# DAC.net
KiCad netlist of a schematic drawn in Altium Designer
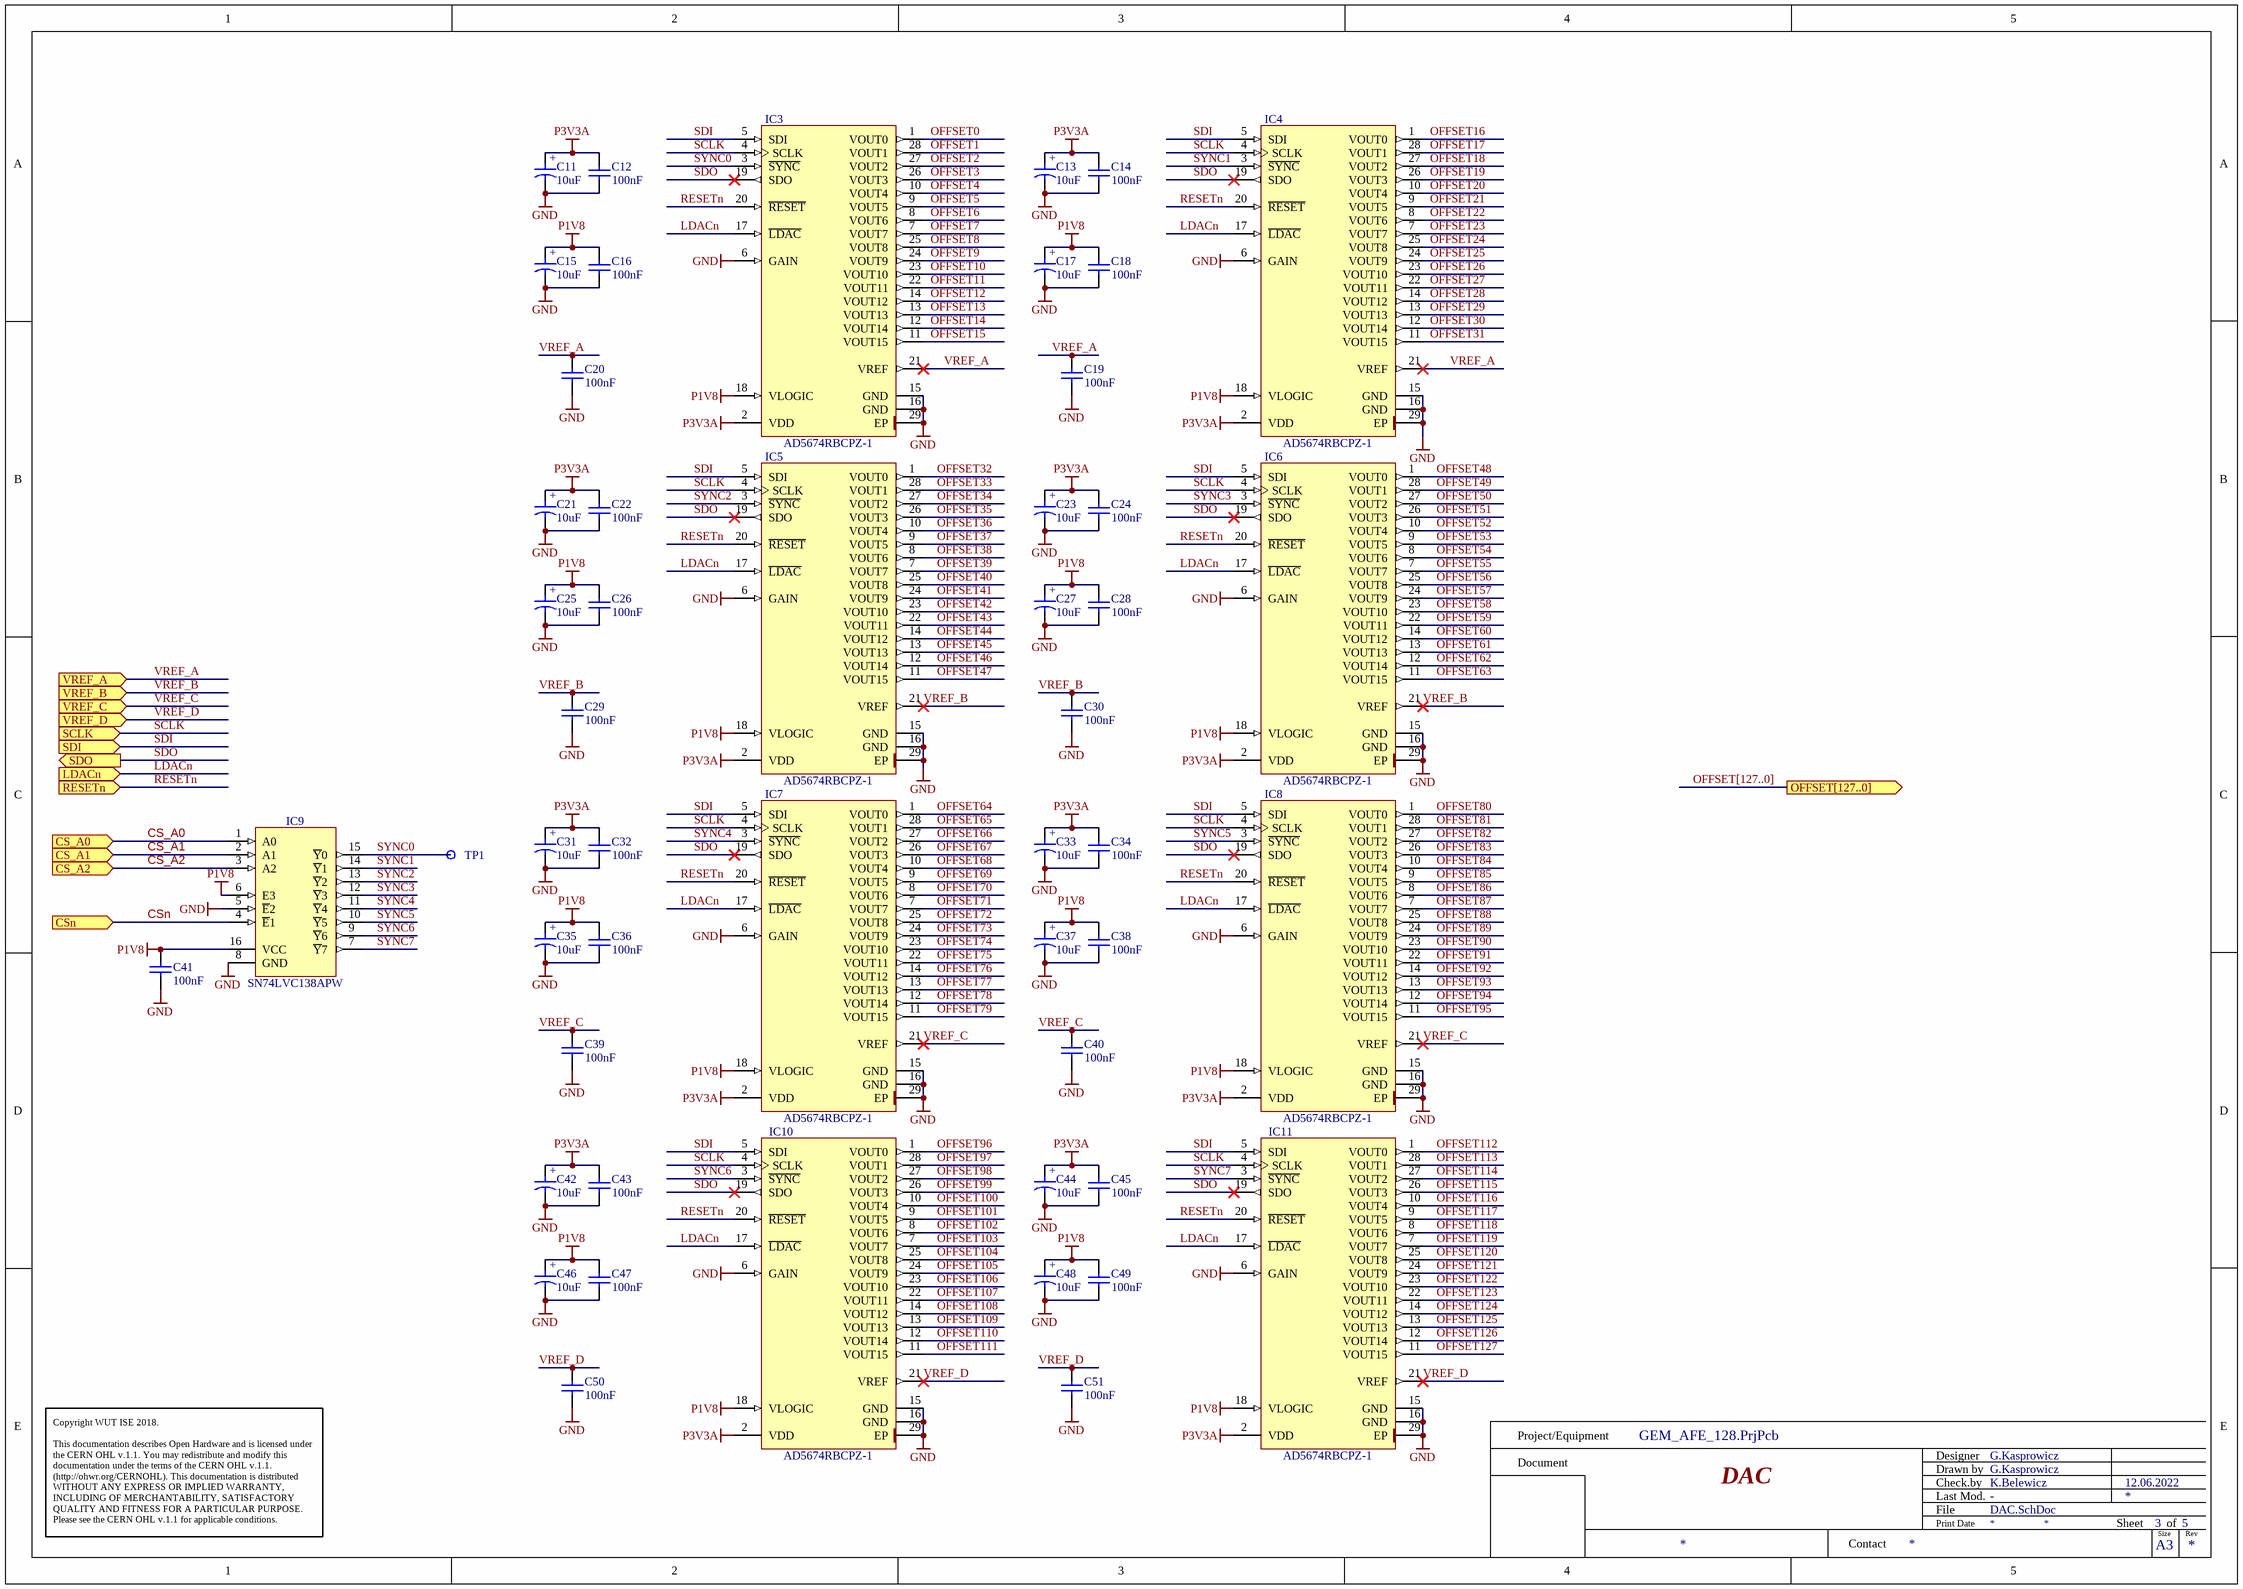
[diagram p0: DAC.SchDoc]

(export (version "E")
  (design (tool "Eeschema 10.0.6"))
  (components
    (comp (ref "C11")
      (value "10uF")
      (footprint "CAPMP3216X180N")
      (description "Polarised capacitor")
      (fields
        (field (name "PART NUMBER") "CTE3216-18_10UF_16V_20%_AVX_TCJ")
        (field (name "VOLTAGE") "16V")
        (field (name "AUTHOR") "CERN DEM JLC")
      )
      (libsource (lib "Capacitors") (part "Capacitor - polarized"))
    )
    (comp (ref "C12")
      (value "100nF")
      (footprint "CAPC1005X55N")
      (description "Non-polarised capacitor")
      (fields
        (field (name "PART NUMBER") "CC0402_100NF_6.3V_10%_X7R")
        (field (name "VOLTAGE") "6.3V")
        (field (name "AUTHOR") "CERN DEM BC")
      )
      (libsource (lib "Capacitors") (part "Capacitor - non polarized"))
    )
    (comp (ref "C13")
      (value "10uF")
      (footprint "CAPMP3216X180N")
      (description "Polarised capacitor")
      (fields
        (field (name "PART NUMBER") "CTE3216-18_10UF_16V_20%_AVX_TCJ")
        (field (name "VOLTAGE") "16V")
        (field (name "AUTHOR") "CERN DEM JLC")
      )
      (libsource (lib "Capacitors") (part "Capacitor - polarized"))
    )
    (comp (ref "C14")
      (value "100nF")
      (footprint "CAPC1005X55N")
      (description "Non-polarised capacitor")
      (fields
        (field (name "PART NUMBER") "CC0402_100NF_6.3V_10%_X7R")
        (field (name "VOLTAGE") "6.3V")
        (field (name "AUTHOR") "CERN DEM BC")
      )
      (libsource (lib "Capacitors") (part "Capacitor - non polarized"))
    )
    (comp (ref "C15")
      (value "10uF")
      (footprint "CAPMP3216X180N")
      (description "Polarised capacitor")
      (fields
        (field (name "PART NUMBER") "CTE3216-18_10UF_16V_20%_AVX_TCJ")
        (field (name "VOLTAGE") "16V")
        (field (name "AUTHOR") "CERN DEM JLC")
      )
      (libsource (lib "Capacitors") (part "Capacitor - polarized"))
    )
    (comp (ref "C16")
      (value "100nF")
      (footprint "CAPC1005X55N")
      (description "Non-polarised capacitor")
      (fields
        (field (name "PART NUMBER") "CC0402_100NF_6.3V_10%_X7R")
        (field (name "VOLTAGE") "6.3V")
        (field (name "AUTHOR") "CERN DEM BC")
      )
      (libsource (lib "Capacitors") (part "Capacitor - non polarized"))
    )
    (comp (ref "C17")
      (value "10uF")
      (footprint "CAPMP3216X180N")
      (description "Polarised capacitor")
      (fields
        (field (name "PART NUMBER") "CTE3216-18_10UF_16V_20%_AVX_TCJ")
        (field (name "VOLTAGE") "16V")
        (field (name "AUTHOR") "CERN DEM JLC")
      )
      (libsource (lib "Capacitors") (part "Capacitor - polarized"))
    )
    (comp (ref "C18")
      (value "100nF")
      (footprint "CAPC1005X55N")
      (description "Non-polarised capacitor")
      (fields
        (field (name "PART NUMBER") "CC0402_100NF_6.3V_10%_X7R")
        (field (name "VOLTAGE") "6.3V")
        (field (name "AUTHOR") "CERN DEM BC")
      )
      (libsource (lib "Capacitors") (part "Capacitor - non polarized"))
    )
    (comp (ref "C19")
      (value "100nF")
      (footprint "CAPC1005X55N")
      (description "Non-polarised capacitor")
      (fields
        (field (name "PART NUMBER") "CC0402_100NF_6.3V_10%_X7R")
        (field (name "VOLTAGE") "6.3V")
        (field (name "AUTHOR") "CERN DEM BC")
      )
      (libsource (lib "Capacitors") (part "Capacitor - non polarized"))
    )
    (comp (ref "C20")
      (value "100nF")
      (footprint "CAPC1005X55N")
      (description "Non-polarised capacitor")
      (fields
        (field (name "PART NUMBER") "CC0402_100NF_6.3V_10%_X7R")
        (field (name "VOLTAGE") "6.3V")
        (field (name "AUTHOR") "CERN DEM BC")
      )
      (libsource (lib "Capacitors") (part "Capacitor - non polarized"))
    )
    (comp (ref "C21")
      (value "10uF")
      (footprint "CAPMP3216X180N")
      (description "Polarised capacitor")
      (fields
        (field (name "PART NUMBER") "CTE3216-18_10UF_16V_20%_AVX_TCJ")
        (field (name "VOLTAGE") "16V")
        (field (name "AUTHOR") "CERN DEM JLC")
      )
      (libsource (lib "Capacitors") (part "Capacitor - polarized"))
    )
    (comp (ref "C22")
      (value "100nF")
      (footprint "CAPC1005X55N")
      (description "Non-polarised capacitor")
      (fields
        (field (name "PART NUMBER") "CC0402_100NF_6.3V_10%_X7R")
        (field (name "VOLTAGE") "6.3V")
        (field (name "AUTHOR") "CERN DEM BC")
      )
      (libsource (lib "Capacitors") (part "Capacitor - non polarized"))
    )
    (comp (ref "C23")
      (value "10uF")
      (footprint "CAPMP3216X180N")
      (description "Polarised capacitor")
      (fields
        (field (name "PART NUMBER") "CTE3216-18_10UF_16V_20%_AVX_TCJ")
        (field (name "VOLTAGE") "16V")
        (field (name "AUTHOR") "CERN DEM JLC")
      )
      (libsource (lib "Capacitors") (part "Capacitor - polarized"))
    )
    (comp (ref "C24")
      (value "100nF")
      (footprint "CAPC1005X55N")
      (description "Non-polarised capacitor")
      (fields
        (field (name "PART NUMBER") "CC0402_100NF_6.3V_10%_X7R")
        (field (name "VOLTAGE") "6.3V")
        (field (name "AUTHOR") "CERN DEM BC")
      )
      (libsource (lib "Capacitors") (part "Capacitor - non polarized"))
    )
    (comp (ref "C25")
      (value "10uF")
      (footprint "CAPMP3216X180N")
      (description "Polarised capacitor")
      (fields
        (field (name "PART NUMBER") "CTE3216-18_10UF_16V_20%_AVX_TCJ")
        (field (name "VOLTAGE") "16V")
        (field (name "AUTHOR") "CERN DEM JLC")
      )
      (libsource (lib "Capacitors") (part "Capacitor - polarized"))
    )
    (comp (ref "C26")
      (value "100nF")
      (footprint "CAPC1005X55N")
      (description "Non-polarised capacitor")
      (fields
        (field (name "PART NUMBER") "CC0402_100NF_6.3V_10%_X7R")
        (field (name "VOLTAGE") "6.3V")
        (field (name "AUTHOR") "CERN DEM BC")
      )
      (libsource (lib "Capacitors") (part "Capacitor - non polarized"))
    )
    (comp (ref "C27")
      (value "10uF")
      (footprint "CAPMP3216X180N")
      (description "Polarised capacitor")
      (fields
        (field (name "PART NUMBER") "CTE3216-18_10UF_16V_20%_AVX_TCJ")
        (field (name "VOLTAGE") "16V")
        (field (name "AUTHOR") "CERN DEM JLC")
      )
      (libsource (lib "Capacitors") (part "Capacitor - polarized"))
    )
    (comp (ref "C28")
      (value "100nF")
      (footprint "CAPC1005X55N")
      (description "Non-polarised capacitor")
      (fields
        (field (name "PART NUMBER") "CC0402_100NF_6.3V_10%_X7R")
        (field (name "VOLTAGE") "6.3V")
        (field (name "AUTHOR") "CERN DEM BC")
      )
      (libsource (lib "Capacitors") (part "Capacitor - non polarized"))
    )
    (comp (ref "C29")
      (value "100nF")
      (footprint "CAPC1005X55N")
      (description "Non-polarised capacitor")
      (fields
        (field (name "PART NUMBER") "CC0402_100NF_6.3V_10%_X7R")
        (field (name "VOLTAGE") "6.3V")
        (field (name "AUTHOR") "CERN DEM BC")
      )
      (libsource (lib "Capacitors") (part "Capacitor - non polarized"))
    )
    (comp (ref "C30")
      (value "100nF")
      (footprint "CAPC1005X55N")
      (description "Non-polarised capacitor")
      (fields
        (field (name "PART NUMBER") "CC0402_100NF_6.3V_10%_X7R")
        (field (name "VOLTAGE") "6.3V")
        (field (name "AUTHOR") "CERN DEM BC")
      )
      (libsource (lib "Capacitors") (part "Capacitor - non polarized"))
    )
    (comp (ref "C31")
      (value "10uF")
      (footprint "CAPMP3216X180N")
      (description "Polarised capacitor")
      (fields
        (field (name "PART NUMBER") "CTE3216-18_10UF_16V_20%_AVX_TCJ")
        (field (name "VOLTAGE") "16V")
        (field (name "AUTHOR") "CERN DEM JLC")
      )
      (libsource (lib "Capacitors") (part "Capacitor - polarized"))
    )
    (comp (ref "C32")
      (value "100nF")
      (footprint "CAPC1005X55N")
      (description "Non-polarised capacitor")
      (fields
        (field (name "PART NUMBER") "CC0402_100NF_6.3V_10%_X7R")
        (field (name "VOLTAGE") "6.3V")
        (field (name "AUTHOR") "CERN DEM BC")
      )
      (libsource (lib "Capacitors") (part "Capacitor - non polarized"))
    )
    (comp (ref "C33")
      (value "10uF")
      (footprint "CAPMP3216X180N")
      (description "Polarised capacitor")
      (fields
        (field (name "PART NUMBER") "CTE3216-18_10UF_16V_20%_AVX_TCJ")
        (field (name "VOLTAGE") "16V")
        (field (name "AUTHOR") "CERN DEM JLC")
      )
      (libsource (lib "Capacitors") (part "Capacitor - polarized"))
    )
    (comp (ref "C34")
      (value "100nF")
      (footprint "CAPC1005X55N")
      (description "Non-polarised capacitor")
      (fields
        (field (name "PART NUMBER") "CC0402_100NF_6.3V_10%_X7R")
        (field (name "VOLTAGE") "6.3V")
        (field (name "AUTHOR") "CERN DEM BC")
      )
      (libsource (lib "Capacitors") (part "Capacitor - non polarized"))
    )
    (comp (ref "C35")
      (value "10uF")
      (footprint "CAPMP3216X180N")
      (description "Polarised capacitor")
      (fields
        (field (name "PART NUMBER") "CTE3216-18_10UF_16V_20%_AVX_TCJ")
        (field (name "VOLTAGE") "16V")
        (field (name "AUTHOR") "CERN DEM JLC")
      )
      (libsource (lib "Capacitors") (part "Capacitor - polarized"))
    )
    (comp (ref "C36")
      (value "100nF")
      (footprint "CAPC1005X55N")
      (description "Non-polarised capacitor")
      (fields
        (field (name "PART NUMBER") "CC0402_100NF_6.3V_10%_X7R")
        (field (name "VOLTAGE") "6.3V")
        (field (name "AUTHOR") "CERN DEM BC")
      )
      (libsource (lib "Capacitors") (part "Capacitor - non polarized"))
    )
    (comp (ref "C37")
      (value "10uF")
      (footprint "CAPMP3216X180N")
      (description "Polarised capacitor")
      (fields
        (field (name "PART NUMBER") "CTE3216-18_10UF_16V_20%_AVX_TCJ")
        (field (name "VOLTAGE") "16V")
        (field (name "AUTHOR") "CERN DEM JLC")
      )
      (libsource (lib "Capacitors") (part "Capacitor - polarized"))
    )
    (comp (ref "C38")
      (value "100nF")
      (footprint "CAPC1005X55N")
      (description "Non-polarised capacitor")
      (fields
        (field (name "PART NUMBER") "CC0402_100NF_6.3V_10%_X7R")
        (field (name "VOLTAGE") "6.3V")
        (field (name "AUTHOR") "CERN DEM BC")
      )
      (libsource (lib "Capacitors") (part "Capacitor - non polarized"))
    )
    (comp (ref "C39")
      (value "100nF")
      (footprint "CAPC1005X55N")
      (description "Non-polarised capacitor")
      (fields
        (field (name "PART NUMBER") "CC0402_100NF_6.3V_10%_X7R")
        (field (name "VOLTAGE") "6.3V")
        (field (name "AUTHOR") "CERN DEM BC")
      )
      (libsource (lib "Capacitors") (part "Capacitor - non polarized"))
    )
    (comp (ref "C40")
      (value "100nF")
      (footprint "CAPC1005X55N")
      (description "Non-polarised capacitor")
      (fields
        (field (name "PART NUMBER") "CC0402_100NF_6.3V_10%_X7R")
        (field (name "VOLTAGE") "6.3V")
        (field (name "AUTHOR") "CERN DEM BC")
      )
      (libsource (lib "Capacitors") (part "Capacitor - non polarized"))
    )
    (comp (ref "C41")
      (value "100nF")
      (footprint "CAPC1005X55N")
      (description "Non-polarised capacitor")
      (fields
        (field (name "PART NUMBER") "CC0402_100NF_16V_10%_X5R")
        (field (name "VOLTAGE") "16V")
        (field (name "AUTHOR") "CERN DEM JLC")
      )
      (libsource (lib "Capacitors") (part "Capacitor - non polarized"))
    )
    (comp (ref "C42")
      (value "10uF")
      (footprint "CAPMP3216X180N")
      (description "Polarised capacitor")
      (fields
        (field (name "PART NUMBER") "CTE3216-18_10UF_16V_20%_AVX_TCJ")
        (field (name "VOLTAGE") "16V")
        (field (name "AUTHOR") "CERN DEM JLC")
      )
      (libsource (lib "Capacitors") (part "Capacitor - polarized"))
    )
    (comp (ref "C43")
      (value "100nF")
      (footprint "CAPC1005X55N")
      (description "Non-polarised capacitor")
      (fields
        (field (name "PART NUMBER") "CC0402_100NF_6.3V_10%_X7R")
        (field (name "VOLTAGE") "6.3V")
        (field (name "AUTHOR") "CERN DEM BC")
      )
      (libsource (lib "Capacitors") (part "Capacitor - non polarized"))
    )
    (comp (ref "C44")
      (value "10uF")
      (footprint "CAPMP3216X180N")
      (description "Polarised capacitor")
      (fields
        (field (name "PART NUMBER") "CTE3216-18_10UF_16V_20%_AVX_TCJ")
        (field (name "VOLTAGE") "16V")
        (field (name "AUTHOR") "CERN DEM JLC")
      )
      (libsource (lib "Capacitors") (part "Capacitor - polarized"))
    )
    (comp (ref "C45")
      (value "100nF")
      (footprint "CAPC1005X55N")
      (description "Non-polarised capacitor")
      (fields
        (field (name "PART NUMBER") "CC0402_100NF_6.3V_10%_X7R")
        (field (name "VOLTAGE") "6.3V")
        (field (name "AUTHOR") "CERN DEM BC")
      )
      (libsource (lib "Capacitors") (part "Capacitor - non polarized"))
    )
    (comp (ref "C46")
      (value "10uF")
      (footprint "CAPMP3216X180N")
      (description "Polarised capacitor")
      (fields
        (field (name "PART NUMBER") "CTE3216-18_10UF_16V_20%_AVX_TCJ")
        (field (name "VOLTAGE") "16V")
        (field (name "AUTHOR") "CERN DEM JLC")
      )
      (libsource (lib "Capacitors") (part "Capacitor - polarized"))
    )
    (comp (ref "C47")
      (value "100nF")
      (footprint "CAPC1005X55N")
      (description "Non-polarised capacitor")
      (fields
        (field (name "PART NUMBER") "CC0402_100NF_6.3V_10%_X7R")
        (field (name "VOLTAGE") "6.3V")
        (field (name "AUTHOR") "CERN DEM BC")
      )
      (libsource (lib "Capacitors") (part "Capacitor - non polarized"))
    )
    (comp (ref "C48")
      (value "10uF")
      (footprint "CAPMP3216X180N")
      (description "Polarised capacitor")
      (fields
        (field (name "PART NUMBER") "CTE3216-18_10UF_16V_20%_AVX_TCJ")
        (field (name "VOLTAGE") "16V")
        (field (name "AUTHOR") "CERN DEM JLC")
      )
      (libsource (lib "Capacitors") (part "Capacitor - polarized"))
    )
    (comp (ref "C49")
      (value "100nF")
      (footprint "CAPC1005X55N")
      (description "Non-polarised capacitor")
      (fields
        (field (name "PART NUMBER") "CC0402_100NF_6.3V_10%_X7R")
        (field (name "VOLTAGE") "6.3V")
        (field (name "AUTHOR") "CERN DEM BC")
      )
      (libsource (lib "Capacitors") (part "Capacitor - non polarized"))
    )
    (comp (ref "C50")
      (value "100nF")
      (footprint "CAPC1005X55N")
      (description "Non-polarised capacitor")
      (fields
        (field (name "PART NUMBER") "CC0402_100NF_6.3V_10%_X7R")
        (field (name "VOLTAGE") "6.3V")
        (field (name "AUTHOR") "CERN DEM BC")
      )
      (libsource (lib "Capacitors") (part "Capacitor - non polarized"))
    )
    (comp (ref "C51")
      (value "100nF")
      (footprint "CAPC1005X55N")
      (description "Non-polarised capacitor")
      (fields
        (field (name "PART NUMBER") "CC0402_100NF_6.3V_10%_X7R")
        (field (name "VOLTAGE") "6.3V")
        (field (name "AUTHOR") "CERN DEM BC")
      )
      (libsource (lib "Capacitors") (part "Capacitor - non polarized"))
    )
    (comp (ref "IC3")
      (value "AD5674RBCPZ-1")
      (footprint "QFN40P400X400X100-29N-S270")
      (description "12-Bit nanoDAC+ with 2 ppm/°C Voltage Reference Temperature Coefficient, SPI Interface")
      (fields (field (name "MANUFACTURER") "ANALOG DEVICES") (field (name "AUTHOR") "CERN DEM HF"))
      (libsource (lib "ICs And Semiconductors") (part "AD5674RBCPZ-1"))
    )
    (comp (ref "IC4")
      (value "AD5674RBCPZ-1")
      (footprint "QFN40P400X400X100-29N-S270")
      (description "12-Bit nanoDAC+ with 2 ppm/°C Voltage Reference Temperature Coefficient, SPI Interface")
      (fields (field (name "MANUFACTURER") "ANALOG DEVICES") (field (name "AUTHOR") "CERN DEM HF"))
      (libsource (lib "ICs And Semiconductors") (part "AD5674RBCPZ-1"))
    )
    (comp (ref "IC5")
      (value "AD5674RBCPZ-1")
      (footprint "QFN40P400X400X100-29N-S270")
      (description "12-Bit nanoDAC+ with 2 ppm/°C Voltage Reference Temperature Coefficient, SPI Interface")
      (fields (field (name "MANUFACTURER") "ANALOG DEVICES") (field (name "AUTHOR") "CERN DEM HF"))
      (libsource (lib "ICs And Semiconductors") (part "AD5674RBCPZ-1"))
    )
    (comp (ref "IC6")
      (value "AD5674RBCPZ-1")
      (footprint "QFN40P400X400X100-29N-S270")
      (description "12-Bit nanoDAC+ with 2 ppm/°C Voltage Reference Temperature Coefficient, SPI Interface")
      (fields (field (name "MANUFACTURER") "ANALOG DEVICES") (field (name "AUTHOR") "CERN DEM HF"))
      (libsource (lib "ICs And Semiconductors") (part "AD5674RBCPZ-1"))
    )
    (comp (ref "IC7")
      (value "AD5674RBCPZ-1")
      (footprint "QFN40P400X400X100-29N-S270")
      (description "12-Bit nanoDAC+ with 2 ppm/°C Voltage Reference Temperature Coefficient, SPI Interface")
      (fields (field (name "MANUFACTURER") "ANALOG DEVICES") (field (name "AUTHOR") "CERN DEM HF"))
      (libsource (lib "ICs And Semiconductors") (part "AD5674RBCPZ-1"))
    )
    (comp (ref "IC8")
      (value "AD5674RBCPZ-1")
      (footprint "QFN40P400X400X100-29N-S270")
      (description "12-Bit nanoDAC+ with 2 ppm/°C Voltage Reference Temperature Coefficient, SPI Interface")
      (fields (field (name "MANUFACTURER") "ANALOG DEVICES") (field (name "AUTHOR") "CERN DEM HF"))
      (libsource (lib "ICs And Semiconductors") (part "AD5674RBCPZ-1"))
    )
    (comp (ref "IC9")
      (value "SN74LVC138APW")
      (footprint "SOP65P640X110-16N")
      (description "3-Line to 8-Line Decoder/Demultiplexer")
      (fields (field (name "MANUFACTURER") "Texas Instruments") (field (name "AUTHOR") "GK"))
      (libsource (lib "ICS-logic") (part "SN74LVC138APW"))
    )
    (comp (ref "IC10")
      (value "AD5674RBCPZ-1")
      (footprint "QFN40P400X400X100-29N-S270")
      (description "12-Bit nanoDAC+ with 2 ppm/°C Voltage Reference Temperature Coefficient, SPI Interface")
      (fields (field (name "MANUFACTURER") "ANALOG DEVICES") (field (name "AUTHOR") "CERN DEM HF"))
      (libsource (lib "ICs And Semiconductors") (part "AD5674RBCPZ-1"))
    )
    (comp (ref "IC11")
      (value "AD5674RBCPZ-1")
      (footprint "QFN40P400X400X100-29N-S270")
      (description "12-Bit nanoDAC+ with 2 ppm/°C Voltage Reference Temperature Coefficient, SPI Interface")
      (fields (field (name "MANUFACTURER") "ANALOG DEVICES") (field (name "AUTHOR") "CERN DEM HF"))
      (libsource (lib "ICs And Semiconductors") (part "AD5674RBCPZ-1"))
    )
    (comp (ref "TP1")
      (value "Test Point")
      (footprint "TPS127")
      (fields (field (name "PART NUMBER") "SMD_PAD_1.27X1.27MM") (field (name "AUTHOR") "CERN DEM JLC"))
      (libsource (lib "Eletro-mechanical") (part "Test Point"))
    )
  )
  (nets
    (net (code "1") (name "/CS_A0") (class "Default")
      (node (ref "IC9") (pin "1") (pinfunction "A0_1") (pintype "input"))
    )
    (net (code "2") (name "/CS_A1") (class "Default")
      (node (ref "IC9") (pin "2") (pinfunction "A1_2") (pintype "input"))
    )
    (net (code "3") (name "/CS_A2") (class "Default")
      (node (ref "IC9") (pin "3") (pinfunction "A2_3") (pintype "input"))
    )
    (net (code "4") (name "/CSn") (class "Default")
      (node (ref "IC9") (pin "4") (pinfunction "~{E}1_4") (pintype "input"))
    )
    (net (code "5") (name "/LDACn") (class "Default")
      (node (ref "IC10") (pin "17") (pinfunction "~{LDAC}_17") (pintype "input"))
      (node (ref "IC11") (pin "17") (pinfunction "~{LDAC}_17") (pintype "input"))
      (node (ref "IC3") (pin "17") (pinfunction "~{LDAC}_17") (pintype "input"))
      (node (ref "IC4") (pin "17") (pinfunction "~{LDAC}_17") (pintype "input"))
      (node (ref "IC5") (pin "17") (pinfunction "~{LDAC}_17") (pintype "input"))
      (node (ref "IC6") (pin "17") (pinfunction "~{LDAC}_17") (pintype "input"))
      (node (ref "IC7") (pin "17") (pinfunction "~{LDAC}_17") (pintype "input"))
      (node (ref "IC8") (pin "17") (pinfunction "~{LDAC}_17") (pintype "input"))
    )
    (net (code "6") (name "/OFFSET0") (class "Default")
      (node (ref "IC3") (pin "1") (pinfunction "VOUT0_1") (pintype "output"))
    )
    (net (code "7") (name "/OFFSET1") (class "Default")
      (node (ref "IC3") (pin "28") (pinfunction "VOUT1_28") (pintype "output"))
    )
    (net (code "8") (name "/OFFSET2") (class "Default")
      (node (ref "IC3") (pin "27") (pinfunction "VOUT2_27") (pintype "output"))
    )
    (net (code "9") (name "/OFFSET3") (class "Default")
      (node (ref "IC3") (pin "26") (pinfunction "VOUT3_26") (pintype "output"))
    )
    (net (code "10") (name "/OFFSET4") (class "Default")
      (node (ref "IC3") (pin "10") (pinfunction "VOUT4_10") (pintype "output"))
    )
    (net (code "11") (name "/OFFSET5") (class "Default")
      (node (ref "IC3") (pin "9") (pinfunction "VOUT5_9") (pintype "output"))
    )
    (net (code "12") (name "/OFFSET6") (class "Default")
      (node (ref "IC3") (pin "8") (pinfunction "VOUT6_8") (pintype "output"))
    )
    (net (code "13") (name "/OFFSET7") (class "Default")
      (node (ref "IC3") (pin "7") (pinfunction "VOUT7_7") (pintype "output"))
    )
    (net (code "14") (name "/OFFSET8") (class "Default")
      (node (ref "IC3") (pin "25") (pinfunction "VOUT8_25") (pintype "output"))
    )
    (net (code "15") (name "/OFFSET9") (class "Default")
      (node (ref "IC3") (pin "24") (pinfunction "VOUT9_24") (pintype "output"))
    )
    (net (code "16") (name "/OFFSET10") (class "Default")
      (node (ref "IC3") (pin "23") (pinfunction "VOUT10_23") (pintype "output"))
    )
    (net (code "17") (name "/OFFSET11") (class "Default")
      (node (ref "IC3") (pin "22") (pinfunction "VOUT11_22") (pintype "output"))
    )
    (net (code "18") (name "/OFFSET12") (class "Default")
      (node (ref "IC3") (pin "14") (pinfunction "VOUT12_14") (pintype "output"))
    )
    (net (code "19") (name "/OFFSET13") (class "Default")
      (node (ref "IC3") (pin "13") (pinfunction "VOUT13_13") (pintype "output"))
    )
    (net (code "20") (name "/OFFSET14") (class "Default")
      (node (ref "IC3") (pin "12") (pinfunction "VOUT14_12") (pintype "output"))
    )
    (net (code "21") (name "/OFFSET15") (class "Default")
      (node (ref "IC3") (pin "11") (pinfunction "VOUT15_11") (pintype "output"))
    )
    (net (code "22") (name "/OFFSET16") (class "Default")
      (node (ref "IC4") (pin "1") (pinfunction "VOUT0_1") (pintype "output"))
    )
    (net (code "23") (name "/OFFSET17") (class "Default")
      (node (ref "IC4") (pin "28") (pinfunction "VOUT1_28") (pintype "output"))
    )
    (net (code "24") (name "/OFFSET18") (class "Default")
      (node (ref "IC4") (pin "27") (pinfunction "VOUT2_27") (pintype "output"))
    )
    (net (code "25") (name "/OFFSET19") (class "Default")
      (node (ref "IC4") (pin "26") (pinfunction "VOUT3_26") (pintype "output"))
    )
    (net (code "26") (name "/OFFSET20") (class "Default")
      (node (ref "IC4") (pin "10") (pinfunction "VOUT4_10") (pintype "output"))
    )
    (net (code "27") (name "/OFFSET21") (class "Default")
      (node (ref "IC4") (pin "9") (pinfunction "VOUT5_9") (pintype "output"))
    )
    (net (code "28") (name "/OFFSET22") (class "Default")
      (node (ref "IC4") (pin "8") (pinfunction "VOUT6_8") (pintype "output"))
    )
    (net (code "29") (name "/OFFSET23") (class "Default")
      (node (ref "IC4") (pin "7") (pinfunction "VOUT7_7") (pintype "output"))
    )
    (net (code "30") (name "/OFFSET24") (class "Default")
      (node (ref "IC4") (pin "25") (pinfunction "VOUT8_25") (pintype "output"))
    )
    (net (code "31") (name "/OFFSET25") (class "Default")
      (node (ref "IC4") (pin "24") (pinfunction "VOUT9_24") (pintype "output"))
    )
    (net (code "32") (name "/OFFSET26") (class "Default")
      (node (ref "IC4") (pin "23") (pinfunction "VOUT10_23") (pintype "output"))
    )
    (net (code "33") (name "/OFFSET27") (class "Default")
      (node (ref "IC4") (pin "22") (pinfunction "VOUT11_22") (pintype "output"))
    )
    (net (code "34") (name "/OFFSET28") (class "Default")
      (node (ref "IC4") (pin "14") (pinfunction "VOUT12_14") (pintype "output"))
    )
    (net (code "35") (name "/OFFSET29") (class "Default")
      (node (ref "IC4") (pin "13") (pinfunction "VOUT13_13") (pintype "output"))
    )
    (net (code "36") (name "/OFFSET30") (class "Default")
      (node (ref "IC4") (pin "12") (pinfunction "VOUT14_12") (pintype "output"))
    )
    (net (code "37") (name "/OFFSET31") (class "Default")
      (node (ref "IC4") (pin "11") (pinfunction "VOUT15_11") (pintype "output"))
    )
    (net (code "38") (name "/OFFSET32") (class "Default")
      (node (ref "IC5") (pin "1") (pinfunction "VOUT0_1") (pintype "output"))
    )
    (net (code "39") (name "/OFFSET33") (class "Default")
      (node (ref "IC5") (pin "28") (pinfunction "VOUT1_28") (pintype "output"))
    )
    (net (code "40") (name "/OFFSET34") (class "Default")
      (node (ref "IC5") (pin "27") (pinfunction "VOUT2_27") (pintype "output"))
    )
    (net (code "41") (name "/OFFSET35") (class "Default")
      (node (ref "IC5") (pin "26") (pinfunction "VOUT3_26") (pintype "output"))
    )
    (net (code "42") (name "/OFFSET36") (class "Default")
      (node (ref "IC5") (pin "10") (pinfunction "VOUT4_10") (pintype "output"))
    )
    (net (code "43") (name "/OFFSET37") (class "Default")
      (node (ref "IC5") (pin "9") (pinfunction "VOUT5_9") (pintype "output"))
    )
    (net (code "44") (name "/OFFSET38") (class "Default")
      (node (ref "IC5") (pin "8") (pinfunction "VOUT6_8") (pintype "output"))
    )
    (net (code "45") (name "/OFFSET39") (class "Default")
      (node (ref "IC5") (pin "7") (pinfunction "VOUT7_7") (pintype "output"))
    )
    (net (code "46") (name "/OFFSET40") (class "Default")
      (node (ref "IC5") (pin "25") (pinfunction "VOUT8_25") (pintype "output"))
    )
    (net (code "47") (name "/OFFSET41") (class "Default")
      (node (ref "IC5") (pin "24") (pinfunction "VOUT9_24") (pintype "output"))
    )
    (net (code "48") (name "/OFFSET42") (class "Default")
      (node (ref "IC5") (pin "23") (pinfunction "VOUT10_23") (pintype "output"))
    )
    (net (code "49") (name "/OFFSET43") (class "Default")
      (node (ref "IC5") (pin "22") (pinfunction "VOUT11_22") (pintype "output"))
    )
    (net (code "50") (name "/OFFSET44") (class "Default")
      (node (ref "IC5") (pin "14") (pinfunction "VOUT12_14") (pintype "output"))
    )
    (net (code "51") (name "/OFFSET45") (class "Default")
      (node (ref "IC5") (pin "13") (pinfunction "VOUT13_13") (pintype "output"))
    )
    (net (code "52") (name "/OFFSET46") (class "Default")
      (node (ref "IC5") (pin "12") (pinfunction "VOUT14_12") (pintype "output"))
    )
    (net (code "53") (name "/OFFSET47") (class "Default")
      (node (ref "IC5") (pin "11") (pinfunction "VOUT15_11") (pintype "output"))
    )
    (net (code "54") (name "/OFFSET48") (class "Default")
      (node (ref "IC6") (pin "1") (pinfunction "VOUT0_1") (pintype "output"))
    )
    (net (code "55") (name "/OFFSET49") (class "Default")
      (node (ref "IC6") (pin "28") (pinfunction "VOUT1_28") (pintype "output"))
    )
    (net (code "56") (name "/OFFSET50") (class "Default")
      (node (ref "IC6") (pin "27") (pinfunction "VOUT2_27") (pintype "output"))
    )
    (net (code "57") (name "/OFFSET51") (class "Default")
      (node (ref "IC6") (pin "26") (pinfunction "VOUT3_26") (pintype "output"))
    )
    (net (code "58") (name "/OFFSET52") (class "Default")
      (node (ref "IC6") (pin "10") (pinfunction "VOUT4_10") (pintype "output"))
    )
    (net (code "59") (name "/OFFSET53") (class "Default")
      (node (ref "IC6") (pin "9") (pinfunction "VOUT5_9") (pintype "output"))
    )
    (net (code "60") (name "/OFFSET54") (class "Default")
      (node (ref "IC6") (pin "8") (pinfunction "VOUT6_8") (pintype "output"))
    )
    (net (code "61") (name "/OFFSET55") (class "Default")
      (node (ref "IC6") (pin "7") (pinfunction "VOUT7_7") (pintype "output"))
    )
    (net (code "62") (name "/OFFSET56") (class "Default")
      (node (ref "IC6") (pin "25") (pinfunction "VOUT8_25") (pintype "output"))
    )
    (net (code "63") (name "/OFFSET57") (class "Default")
      (node (ref "IC6") (pin "24") (pinfunction "VOUT9_24") (pintype "output"))
    )
    (net (code "64") (name "/OFFSET58") (class "Default")
      (node (ref "IC6") (pin "23") (pinfunction "VOUT10_23") (pintype "output"))
    )
    (net (code "65") (name "/OFFSET59") (class "Default")
      (node (ref "IC6") (pin "22") (pinfunction "VOUT11_22") (pintype "output"))
    )
    (net (code "66") (name "/OFFSET60") (class "Default")
      (node (ref "IC6") (pin "14") (pinfunction "VOUT12_14") (pintype "output"))
    )
    (net (code "67") (name "/OFFSET61") (class "Default")
      (node (ref "IC6") (pin "13") (pinfunction "VOUT13_13") (pintype "output"))
    )
    (net (code "68") (name "/OFFSET62") (class "Default")
      (node (ref "IC6") (pin "12") (pinfunction "VOUT14_12") (pintype "output"))
    )
    (net (code "69") (name "/OFFSET63") (class "Default")
      (node (ref "IC6") (pin "11") (pinfunction "VOUT15_11") (pintype "output"))
    )
    (net (code "70") (name "/OFFSET64") (class "Default")
      (node (ref "IC7") (pin "1") (pinfunction "VOUT0_1") (pintype "output"))
    )
    (net (code "71") (name "/OFFSET65") (class "Default")
      (node (ref "IC7") (pin "28") (pinfunction "VOUT1_28") (pintype "output"))
    )
    (net (code "72") (name "/OFFSET66") (class "Default")
      (node (ref "IC7") (pin "27") (pinfunction "VOUT2_27") (pintype "output"))
    )
    (net (code "73") (name "/OFFSET67") (class "Default")
      (node (ref "IC7") (pin "26") (pinfunction "VOUT3_26") (pintype "output"))
    )
    (net (code "74") (name "/OFFSET68") (class "Default")
      (node (ref "IC7") (pin "10") (pinfunction "VOUT4_10") (pintype "output"))
    )
    (net (code "75") (name "/OFFSET69") (class "Default")
      (node (ref "IC7") (pin "9") (pinfunction "VOUT5_9") (pintype "output"))
    )
    (net (code "76") (name "/OFFSET70") (class "Default")
      (node (ref "IC7") (pin "8") (pinfunction "VOUT6_8") (pintype "output"))
    )
    (net (code "77") (name "/OFFSET71") (class "Default")
      (node (ref "IC7") (pin "7") (pinfunction "VOUT7_7") (pintype "output"))
    )
    (net (code "78") (name "/OFFSET72") (class "Default")
      (node (ref "IC7") (pin "25") (pinfunction "VOUT8_25") (pintype "output"))
    )
    (net (code "79") (name "/OFFSET73") (class "Default")
      (node (ref "IC7") (pin "24") (pinfunction "VOUT9_24") (pintype "output"))
    )
    (net (code "80") (name "/OFFSET74") (class "Default")
      (node (ref "IC7") (pin "23") (pinfunction "VOUT10_23") (pintype "output"))
    )
    (net (code "81") (name "/OFFSET75") (class "Default")
      (node (ref "IC7") (pin "22") (pinfunction "VOUT11_22") (pintype "output"))
    )
    (net (code "82") (name "/OFFSET76") (class "Default")
      (node (ref "IC7") (pin "14") (pinfunction "VOUT12_14") (pintype "output"))
    )
    (net (code "83") (name "/OFFSET77") (class "Default")
      (node (ref "IC7") (pin "13") (pinfunction "VOUT13_13") (pintype "output"))
    )
    (net (code "84") (name "/OFFSET78") (class "Default")
      (node (ref "IC7") (pin "12") (pinfunction "VOUT14_12") (pintype "output"))
    )
    (net (code "85") (name "/OFFSET79") (class "Default")
      (node (ref "IC7") (pin "11") (pinfunction "VOUT15_11") (pintype "output"))
    )
    (net (code "86") (name "/OFFSET80") (class "Default")
      (node (ref "IC8") (pin "1") (pinfunction "VOUT0_1") (pintype "output"))
    )
    (net (code "87") (name "/OFFSET81") (class "Default")
      (node (ref "IC8") (pin "28") (pinfunction "VOUT1_28") (pintype "output"))
    )
    (net (code "88") (name "/OFFSET82") (class "Default")
      (node (ref "IC8") (pin "27") (pinfunction "VOUT2_27") (pintype "output"))
    )
    (net (code "89") (name "/OFFSET83") (class "Default")
      (node (ref "IC8") (pin "26") (pinfunction "VOUT3_26") (pintype "output"))
    )
    (net (code "90") (name "/OFFSET84") (class "Default")
      (node (ref "IC8") (pin "10") (pinfunction "VOUT4_10") (pintype "output"))
    )
    (net (code "91") (name "/OFFSET85") (class "Default")
      (node (ref "IC8") (pin "9") (pinfunction "VOUT5_9") (pintype "output"))
    )
    (net (code "92") (name "/OFFSET86") (class "Default")
      (node (ref "IC8") (pin "8") (pinfunction "VOUT6_8") (pintype "output"))
    )
    (net (code "93") (name "/OFFSET87") (class "Default")
      (node (ref "IC8") (pin "7") (pinfunction "VOUT7_7") (pintype "output"))
    )
    (net (code "94") (name "/OFFSET88") (class "Default")
      (node (ref "IC8") (pin "25") (pinfunction "VOUT8_25") (pintype "output"))
    )
    (net (code "95") (name "/OFFSET89") (class "Default")
      (node (ref "IC8") (pin "24") (pinfunction "VOUT9_24") (pintype "output"))
    )
    (net (code "96") (name "/OFFSET90") (class "Default")
      (node (ref "IC8") (pin "23") (pinfunction "VOUT10_23") (pintype "output"))
    )
    (net (code "97") (name "/OFFSET91") (class "Default")
      (node (ref "IC8") (pin "22") (pinfunction "VOUT11_22") (pintype "output"))
    )
    (net (code "98") (name "/OFFSET92") (class "Default")
      (node (ref "IC8") (pin "14") (pinfunction "VOUT12_14") (pintype "output"))
    )
    (net (code "99") (name "/OFFSET93") (class "Default")
      (node (ref "IC8") (pin "13") (pinfunction "VOUT13_13") (pintype "output"))
    )
    (net (code "100") (name "/OFFSET94") (class "Default")
      (node (ref "IC8") (pin "12") (pinfunction "VOUT14_12") (pintype "output"))
    )
    (net (code "101") (name "/OFFSET95") (class "Default")
      (node (ref "IC8") (pin "11") (pinfunction "VOUT15_11") (pintype "output"))
    )
    (net (code "102") (name "/OFFSET96") (class "Default")
      (node (ref "IC10") (pin "1") (pinfunction "VOUT0_1") (pintype "output"))
    )
    (net (code "103") (name "/OFFSET97") (class "Default")
      (node (ref "IC10") (pin "28") (pinfunction "VOUT1_28") (pintype "output"))
    )
    (net (code "104") (name "/OFFSET98") (class "Default")
      (node (ref "IC10") (pin "27") (pinfunction "VOUT2_27") (pintype "output"))
    )
    (net (code "105") (name "/OFFSET99") (class "Default")
      (node (ref "IC10") (pin "26") (pinfunction "VOUT3_26") (pintype "output"))
    )
    (net (code "106") (name "/OFFSET100") (class "Default")
      (node (ref "IC10") (pin "10") (pinfunction "VOUT4_10") (pintype "output"))
    )
    (net (code "107") (name "/OFFSET101") (class "Default")
      (node (ref "IC10") (pin "9") (pinfunction "VOUT5_9") (pintype "output"))
    )
    (net (code "108") (name "/OFFSET102") (class "Default")
      (node (ref "IC10") (pin "8") (pinfunction "VOUT6_8") (pintype "output"))
    )
    (net (code "109") (name "/OFFSET103") (class "Default")
      (node (ref "IC10") (pin "7") (pinfunction "VOUT7_7") (pintype "output"))
    )
    (net (code "110") (name "/OFFSET104") (class "Default")
      (node (ref "IC10") (pin "25") (pinfunction "VOUT8_25") (pintype "output"))
    )
    (net (code "111") (name "/OFFSET105") (class "Default")
      (node (ref "IC10") (pin "24") (pinfunction "VOUT9_24") (pintype "output"))
    )
    (net (code "112") (name "/OFFSET106") (class "Default")
      (node (ref "IC10") (pin "23") (pinfunction "VOUT10_23") (pintype "output"))
    )
    (net (code "113") (name "/OFFSET107") (class "Default")
      (node (ref "IC10") (pin "22") (pinfunction "VOUT11_22") (pintype "output"))
    )
    (net (code "114") (name "/OFFSET108") (class "Default")
      (node (ref "IC10") (pin "14") (pinfunction "VOUT12_14") (pintype "output"))
    )
    (net (code "115") (name "/OFFSET109") (class "Default")
      (node (ref "IC10") (pin "13") (pinfunction "VOUT13_13") (pintype "output"))
    )
    (net (code "116") (name "/OFFSET110") (class "Default")
      (node (ref "IC10") (pin "12") (pinfunction "VOUT14_12") (pintype "output"))
    )
    (net (code "117") (name "/OFFSET111") (class "Default")
      (node (ref "IC10") (pin "11") (pinfunction "VOUT15_11") (pintype "output"))
    )
    (net (code "118") (name "/OFFSET112") (class "Default")
      (node (ref "IC11") (pin "1") (pinfunction "VOUT0_1") (pintype "output"))
    )
    (net (code "119") (name "/OFFSET113") (class "Default")
      (node (ref "IC11") (pin "28") (pinfunction "VOUT1_28") (pintype "output"))
    )
    (net (code "120") (name "/OFFSET114") (class "Default")
      (node (ref "IC11") (pin "27") (pinfunction "VOUT2_27") (pintype "output"))
    )
    (net (code "121") (name "/OFFSET115") (class "Default")
      (node (ref "IC11") (pin "26") (pinfunction "VOUT3_26") (pintype "output"))
    )
    (net (code "122") (name "/OFFSET116") (class "Default")
      (node (ref "IC11") (pin "10") (pinfunction "VOUT4_10") (pintype "output"))
    )
    (net (code "123") (name "/OFFSET117") (class "Default")
      (node (ref "IC11") (pin "9") (pinfunction "VOUT5_9") (pintype "output"))
    )
    (net (code "124") (name "/OFFSET118") (class "Default")
      (node (ref "IC11") (pin "8") (pinfunction "VOUT6_8") (pintype "output"))
    )
    (net (code "125") (name "/OFFSET119") (class "Default")
      (node (ref "IC11") (pin "7") (pinfunction "VOUT7_7") (pintype "output"))
    )
    (net (code "126") (name "/OFFSET120") (class "Default")
      (node (ref "IC11") (pin "25") (pinfunction "VOUT8_25") (pintype "output"))
    )
    (net (code "127") (name "/OFFSET121") (class "Default")
      (node (ref "IC11") (pin "24") (pinfunction "VOUT9_24") (pintype "output"))
    )
    (net (code "128") (name "/OFFSET122") (class "Default")
      (node (ref "IC11") (pin "23") (pinfunction "VOUT10_23") (pintype "output"))
    )
    (net (code "129") (name "/OFFSET123") (class "Default")
      (node (ref "IC11") (pin "22") (pinfunction "VOUT11_22") (pintype "output"))
    )
    (net (code "130") (name "/OFFSET124") (class "Default")
      (node (ref "IC11") (pin "14") (pinfunction "VOUT12_14") (pintype "output"))
    )
    (net (code "131") (name "/OFFSET125") (class "Default")
      (node (ref "IC11") (pin "13") (pinfunction "VOUT13_13") (pintype "output"))
    )
    (net (code "132") (name "/OFFSET126") (class "Default")
      (node (ref "IC11") (pin "12") (pinfunction "VOUT14_12") (pintype "output"))
    )
    (net (code "133") (name "/OFFSET127") (class "Default")
      (node (ref "IC11") (pin "11") (pinfunction "VOUT15_11") (pintype "output"))
    )
    (net (code "135") (name "/RESETn") (class "Default")
      (node (ref "IC10") (pin "20") (pinfunction "~{RESET}_20") (pintype "input"))
      (node (ref "IC11") (pin "20") (pinfunction "~{RESET}_20") (pintype "input"))
      (node (ref "IC3") (pin "20") (pinfunction "~{RESET}_20") (pintype "input"))
      (node (ref "IC4") (pin "20") (pinfunction "~{RESET}_20") (pintype "input"))
      (node (ref "IC5") (pin "20") (pinfunction "~{RESET}_20") (pintype "input"))
      (node (ref "IC6") (pin "20") (pinfunction "~{RESET}_20") (pintype "input"))
      (node (ref "IC7") (pin "20") (pinfunction "~{RESET}_20") (pintype "input"))
      (node (ref "IC8") (pin "20") (pinfunction "~{RESET}_20") (pintype "input"))
    )
    (net (code "136") (name "/SCLK") (class "Default")
      (node (ref "IC10") (pin "4") (pinfunction "SCLK_4") (pintype "input"))
      (node (ref "IC11") (pin "4") (pinfunction "SCLK_4") (pintype "input"))
      (node (ref "IC3") (pin "4") (pinfunction "SCLK_4") (pintype "input"))
      (node (ref "IC4") (pin "4") (pinfunction "SCLK_4") (pintype "input"))
      (node (ref "IC5") (pin "4") (pinfunction "SCLK_4") (pintype "input"))
      (node (ref "IC6") (pin "4") (pinfunction "SCLK_4") (pintype "input"))
      (node (ref "IC7") (pin "4") (pinfunction "SCLK_4") (pintype "input"))
      (node (ref "IC8") (pin "4") (pinfunction "SCLK_4") (pintype "input"))
    )
    (net (code "137") (name "/SDI") (class "Default")
      (node (ref "IC10") (pin "5") (pinfunction "SDI_5") (pintype "input"))
      (node (ref "IC11") (pin "5") (pinfunction "SDI_5") (pintype "input"))
      (node (ref "IC3") (pin "5") (pinfunction "SDI_5") (pintype "input"))
      (node (ref "IC4") (pin "5") (pinfunction "SDI_5") (pintype "input"))
      (node (ref "IC5") (pin "5") (pinfunction "SDI_5") (pintype "input"))
      (node (ref "IC6") (pin "5") (pinfunction "SDI_5") (pintype "input"))
      (node (ref "IC7") (pin "5") (pinfunction "SDI_5") (pintype "input"))
      (node (ref "IC8") (pin "5") (pinfunction "SDI_5") (pintype "input"))
    )
    (net (code "138") (name "/SDO") (class "Default")
      (node (ref "IC10") (pin "19") (pinfunction "SDO_19") (pintype "output"))
      (node (ref "IC11") (pin "19") (pinfunction "SDO_19") (pintype "output"))
      (node (ref "IC3") (pin "19") (pinfunction "SDO_19") (pintype "output"))
      (node (ref "IC4") (pin "19") (pinfunction "SDO_19") (pintype "output"))
      (node (ref "IC5") (pin "19") (pinfunction "SDO_19") (pintype "output"))
      (node (ref "IC6") (pin "19") (pinfunction "SDO_19") (pintype "output"))
      (node (ref "IC7") (pin "19") (pinfunction "SDO_19") (pintype "output"))
      (node (ref "IC8") (pin "19") (pinfunction "SDO_19") (pintype "output"))
    )
    (net (code "139") (name "/SYNC0") (class "Default")
      (node (ref "IC3") (pin "3") (pinfunction "~{SYNC}_3") (pintype "input"))
      (node (ref "IC9") (pin "15") (pinfunction "~{Y}0_15") (pintype "output"))
      (node (ref "TP1") (pin "1") (pinfunction "1_1") (pintype "bidirectional"))
    )
    (net (code "140") (name "/SYNC1") (class "Default")
      (node (ref "IC4") (pin "3") (pinfunction "~{SYNC}_3") (pintype "input"))
      (node (ref "IC9") (pin "14") (pinfunction "~{Y}1_14") (pintype "output"))
    )
    (net (code "141") (name "/SYNC2") (class "Default")
      (node (ref "IC5") (pin "3") (pinfunction "~{SYNC}_3") (pintype "input"))
      (node (ref "IC9") (pin "13") (pinfunction "~{Y}2_13") (pintype "output"))
    )
    (net (code "142") (name "/SYNC3") (class "Default")
      (node (ref "IC6") (pin "3") (pinfunction "~{SYNC}_3") (pintype "input"))
      (node (ref "IC9") (pin "12") (pinfunction "~{Y}3_12") (pintype "output"))
    )
    (net (code "143") (name "/SYNC4") (class "Default")
      (node (ref "IC7") (pin "3") (pinfunction "~{SYNC}_3") (pintype "input"))
      (node (ref "IC9") (pin "11") (pinfunction "~{Y}4_11") (pintype "output"))
    )
    (net (code "144") (name "/SYNC5") (class "Default")
      (node (ref "IC8") (pin "3") (pinfunction "~{SYNC}_3") (pintype "input"))
      (node (ref "IC9") (pin "10") (pinfunction "~{Y}5_10") (pintype "output"))
    )
    (net (code "145") (name "/SYNC6") (class "Default")
      (node (ref "IC10") (pin "3") (pinfunction "~{SYNC}_3") (pintype "input"))
      (node (ref "IC9") (pin "9") (pinfunction "~{Y}6_9") (pintype "output"))
    )
    (net (code "146") (name "/SYNC7") (class "Default")
      (node (ref "IC11") (pin "3") (pinfunction "~{SYNC}_3") (pintype "input"))
      (node (ref "IC9") (pin "7") (pinfunction "~{Y}7_7") (pintype "output"))
    )
    (net (code "147") (name "/VREF_A") (class "Default")
      (node (ref "C19") (pin "2") (pinfunction "2_2") (pintype "passive"))
      (node (ref "C20") (pin "2") (pinfunction "2_2") (pintype "passive"))
      (node (ref "IC3") (pin "21") (pinfunction "VREF_21") (pintype "output"))
      (node (ref "IC4") (pin "21") (pinfunction "VREF_21") (pintype "output"))
    )
    (net (code "148") (name "/VREF_B") (class "Default")
      (node (ref "C29") (pin "2") (pinfunction "2_2") (pintype "passive"))
      (node (ref "C30") (pin "2") (pinfunction "2_2") (pintype "passive"))
      (node (ref "IC5") (pin "21") (pinfunction "VREF_21") (pintype "output"))
      (node (ref "IC6") (pin "21") (pinfunction "VREF_21") (pintype "output"))
    )
    (net (code "149") (name "/VREF_C") (class "Default")
      (node (ref "C39") (pin "2") (pinfunction "2_2") (pintype "passive"))
      (node (ref "C40") (pin "2") (pinfunction "2_2") (pintype "passive"))
      (node (ref "IC7") (pin "21") (pinfunction "VREF_21") (pintype "output"))
      (node (ref "IC8") (pin "21") (pinfunction "VREF_21") (pintype "output"))
    )
    (net (code "150") (name "/VREF_D") (class "Default")
      (node (ref "C50") (pin "2") (pinfunction "2_2") (pintype "passive"))
      (node (ref "C51") (pin "2") (pinfunction "2_2") (pintype "passive"))
      (node (ref "IC10") (pin "21") (pinfunction "VREF_21") (pintype "output"))
      (node (ref "IC11") (pin "21") (pinfunction "VREF_21") (pintype "output"))
    )
    (net (code "151") (name "GND") (class "Default")
      (node (ref "C11") (pin "2") (pinfunction "2_2") (pintype "passive"))
      (node (ref "C12") (pin "1") (pinfunction "1_1") (pintype "passive"))
      (node (ref "C13") (pin "2") (pinfunction "2_2") (pintype "passive"))
      (node (ref "C14") (pin "1") (pinfunction "1_1") (pintype "passive"))
      (node (ref "C15") (pin "2") (pinfunction "2_2") (pintype "passive"))
      (node (ref "C16") (pin "1") (pinfunction "1_1") (pintype "passive"))
      (node (ref "C17") (pin "2") (pinfunction "2_2") (pintype "passive"))
      (node (ref "C18") (pin "1") (pinfunction "1_1") (pintype "passive"))
      (node (ref "C19") (pin "1") (pinfunction "1_1") (pintype "passive"))
      (node (ref "C20") (pin "1") (pinfunction "1_1") (pintype "passive"))
      (node (ref "C21") (pin "2") (pinfunction "2_2") (pintype "passive"))
      (node (ref "C22") (pin "1") (pinfunction "1_1") (pintype "passive"))
      (node (ref "C23") (pin "2") (pinfunction "2_2") (pintype "passive"))
      (node (ref "C24") (pin "1") (pinfunction "1_1") (pintype "passive"))
      (node (ref "C25") (pin "2") (pinfunction "2_2") (pintype "passive"))
      (node (ref "C26") (pin "1") (pinfunction "1_1") (pintype "passive"))
      (node (ref "C27") (pin "2") (pinfunction "2_2") (pintype "passive"))
      (node (ref "C28") (pin "1") (pinfunction "1_1") (pintype "passive"))
      (node (ref "C29") (pin "1") (pinfunction "1_1") (pintype "passive"))
      (node (ref "C30") (pin "1") (pinfunction "1_1") (pintype "passive"))
      (node (ref "C31") (pin "2") (pinfunction "2_2") (pintype "passive"))
      (node (ref "C32") (pin "1") (pinfunction "1_1") (pintype "passive"))
      (node (ref "C33") (pin "2") (pinfunction "2_2") (pintype "passive"))
      (node (ref "C34") (pin "1") (pinfunction "1_1") (pintype "passive"))
      (node (ref "C35") (pin "2") (pinfunction "2_2") (pintype "passive"))
      (node (ref "C36") (pin "1") (pinfunction "1_1") (pintype "passive"))
      (node (ref "C37") (pin "2") (pinfunction "2_2") (pintype "passive"))
      (node (ref "C38") (pin "1") (pinfunction "1_1") (pintype "passive"))
      (node (ref "C39") (pin "1") (pinfunction "1_1") (pintype "passive"))
      (node (ref "C40") (pin "1") (pinfunction "1_1") (pintype "passive"))
      (node (ref "C41") (pin "1") (pinfunction "1_1") (pintype "passive"))
      (node (ref "C42") (pin "2") (pinfunction "2_2") (pintype "passive"))
      (node (ref "C43") (pin "1") (pinfunction "1_1") (pintype "passive"))
      (node (ref "C44") (pin "2") (pinfunction "2_2") (pintype "passive"))
      (node (ref "C45") (pin "1") (pinfunction "1_1") (pintype "passive"))
      (node (ref "C46") (pin "2") (pinfunction "2_2") (pintype "passive"))
      (node (ref "C47") (pin "1") (pinfunction "1_1") (pintype "passive"))
      (node (ref "C48") (pin "2") (pinfunction "2_2") (pintype "passive"))
      (node (ref "C49") (pin "1") (pinfunction "1_1") (pintype "passive"))
      (node (ref "C50") (pin "1") (pinfunction "1_1") (pintype "passive"))
      (node (ref "C51") (pin "1") (pinfunction "1_1") (pintype "passive"))
      (node (ref "IC10") (pin "15") (pinfunction "GND_15") (pintype "power_in"))
      (node (ref "IC10") (pin "16") (pinfunction "GND_16") (pintype "power_in"))
      (node (ref "IC10") (pin "29") (pinfunction "EP_29") (pintype "power_in"))
      (node (ref "IC10") (pin "6") (pinfunction "GAIN_6") (pintype "input"))
      (node (ref "IC11") (pin "15") (pinfunction "GND_15") (pintype "power_in"))
      (node (ref "IC11") (pin "16") (pinfunction "GND_16") (pintype "power_in"))
      (node (ref "IC11") (pin "29") (pinfunction "EP_29") (pintype "power_in"))
      (node (ref "IC11") (pin "6") (pinfunction "GAIN_6") (pintype "input"))
      (node (ref "IC3") (pin "15") (pinfunction "GND_15") (pintype "power_in"))
      (node (ref "IC3") (pin "16") (pinfunction "GND_16") (pintype "power_in"))
      (node (ref "IC3") (pin "29") (pinfunction "EP_29") (pintype "power_in"))
      (node (ref "IC3") (pin "6") (pinfunction "GAIN_6") (pintype "input"))
      (node (ref "IC4") (pin "15") (pinfunction "GND_15") (pintype "power_in"))
      (node (ref "IC4") (pin "16") (pinfunction "GND_16") (pintype "power_in"))
      (node (ref "IC4") (pin "29") (pinfunction "EP_29") (pintype "power_in"))
      (node (ref "IC4") (pin "6") (pinfunction "GAIN_6") (pintype "input"))
      (node (ref "IC5") (pin "15") (pinfunction "GND_15") (pintype "power_in"))
      (node (ref "IC5") (pin "16") (pinfunction "GND_16") (pintype "power_in"))
      (node (ref "IC5") (pin "29") (pinfunction "EP_29") (pintype "power_in"))
      (node (ref "IC5") (pin "6") (pinfunction "GAIN_6") (pintype "input"))
      (node (ref "IC6") (pin "15") (pinfunction "GND_15") (pintype "power_in"))
      (node (ref "IC6") (pin "16") (pinfunction "GND_16") (pintype "power_in"))
      (node (ref "IC6") (pin "29") (pinfunction "EP_29") (pintype "power_in"))
      (node (ref "IC6") (pin "6") (pinfunction "GAIN_6") (pintype "input"))
      (node (ref "IC7") (pin "15") (pinfunction "GND_15") (pintype "power_in"))
      (node (ref "IC7") (pin "16") (pinfunction "GND_16") (pintype "power_in"))
      (node (ref "IC7") (pin "29") (pinfunction "EP_29") (pintype "power_in"))
      (node (ref "IC7") (pin "6") (pinfunction "GAIN_6") (pintype "input"))
      (node (ref "IC8") (pin "15") (pinfunction "GND_15") (pintype "power_in"))
      (node (ref "IC8") (pin "16") (pinfunction "GND_16") (pintype "power_in"))
      (node (ref "IC8") (pin "29") (pinfunction "EP_29") (pintype "power_in"))
      (node (ref "IC8") (pin "6") (pinfunction "GAIN_6") (pintype "input"))
      (node (ref "IC9") (pin "5") (pinfunction "~{E}2_5") (pintype "input"))
      (node (ref "IC9") (pin "8") (pinfunction "GND_8") (pintype "power_in"))
    )
    (net (code "152") (name "P1V8") (class "Default")
      (node (ref "C15") (pin "1") (pinfunction "1_1") (pintype "passive"))
      (node (ref "C16") (pin "2") (pinfunction "2_2") (pintype "passive"))
      (node (ref "C17") (pin "1") (pinfunction "1_1") (pintype "passive"))
      (node (ref "C18") (pin "2") (pinfunction "2_2") (pintype "passive"))
      (node (ref "C25") (pin "1") (pinfunction "1_1") (pintype "passive"))
      (node (ref "C26") (pin "2") (pinfunction "2_2") (pintype "passive"))
      (node (ref "C27") (pin "1") (pinfunction "1_1") (pintype "passive"))
      (node (ref "C28") (pin "2") (pinfunction "2_2") (pintype "passive"))
      (node (ref "C35") (pin "1") (pinfunction "1_1") (pintype "passive"))
      (node (ref "C36") (pin "2") (pinfunction "2_2") (pintype "passive"))
      (node (ref "C37") (pin "1") (pinfunction "1_1") (pintype "passive"))
      (node (ref "C38") (pin "2") (pinfunction "2_2") (pintype "passive"))
      (node (ref "C41") (pin "2") (pinfunction "2_2") (pintype "passive"))
      (node (ref "C46") (pin "1") (pinfunction "1_1") (pintype "passive"))
      (node (ref "C47") (pin "2") (pinfunction "2_2") (pintype "passive"))
      (node (ref "C48") (pin "1") (pinfunction "1_1") (pintype "passive"))
      (node (ref "C49") (pin "2") (pinfunction "2_2") (pintype "passive"))
      (node (ref "IC10") (pin "18") (pinfunction "VLOGIC_18") (pintype "input"))
      (node (ref "IC11") (pin "18") (pinfunction "VLOGIC_18") (pintype "input"))
      (node (ref "IC3") (pin "18") (pinfunction "VLOGIC_18") (pintype "input"))
      (node (ref "IC4") (pin "18") (pinfunction "VLOGIC_18") (pintype "input"))
      (node (ref "IC5") (pin "18") (pinfunction "VLOGIC_18") (pintype "input"))
      (node (ref "IC6") (pin "18") (pinfunction "VLOGIC_18") (pintype "input"))
      (node (ref "IC7") (pin "18") (pinfunction "VLOGIC_18") (pintype "input"))
      (node (ref "IC8") (pin "18") (pinfunction "VLOGIC_18") (pintype "input"))
      (node (ref "IC9") (pin "16") (pinfunction "VCC_16") (pintype "power_in"))
      (node (ref "IC9") (pin "6") (pinfunction "E3_6") (pintype "input"))
    )
    (net (code "153") (name "P3V3A") (class "Default")
      (node (ref "C11") (pin "1") (pinfunction "1_1") (pintype "passive"))
      (node (ref "C12") (pin "2") (pinfunction "2_2") (pintype "passive"))
      (node (ref "C13") (pin "1") (pinfunction "1_1") (pintype "passive"))
      (node (ref "C14") (pin "2") (pinfunction "2_2") (pintype "passive"))
      (node (ref "C21") (pin "1") (pinfunction "1_1") (pintype "passive"))
      (node (ref "C22") (pin "2") (pinfunction "2_2") (pintype "passive"))
      (node (ref "C23") (pin "1") (pinfunction "1_1") (pintype "passive"))
      (node (ref "C24") (pin "2") (pinfunction "2_2") (pintype "passive"))
      (node (ref "C31") (pin "1") (pinfunction "1_1") (pintype "passive"))
      (node (ref "C32") (pin "2") (pinfunction "2_2") (pintype "passive"))
      (node (ref "C33") (pin "1") (pinfunction "1_1") (pintype "passive"))
      (node (ref "C34") (pin "2") (pinfunction "2_2") (pintype "passive"))
      (node (ref "C42") (pin "1") (pinfunction "1_1") (pintype "passive"))
      (node (ref "C43") (pin "2") (pinfunction "2_2") (pintype "passive"))
      (node (ref "C44") (pin "1") (pinfunction "1_1") (pintype "passive"))
      (node (ref "C45") (pin "2") (pinfunction "2_2") (pintype "passive"))
      (node (ref "IC10") (pin "2") (pinfunction "VDD_2") (pintype "power_in"))
      (node (ref "IC11") (pin "2") (pinfunction "VDD_2") (pintype "power_in"))
      (node (ref "IC3") (pin "2") (pinfunction "VDD_2") (pintype "power_in"))
      (node (ref "IC4") (pin "2") (pinfunction "VDD_2") (pintype "power_in"))
      (node (ref "IC5") (pin "2") (pinfunction "VDD_2") (pintype "power_in"))
      (node (ref "IC6") (pin "2") (pinfunction "VDD_2") (pintype "power_in"))
      (node (ref "IC7") (pin "2") (pinfunction "VDD_2") (pintype "power_in"))
      (node (ref "IC8") (pin "2") (pinfunction "VDD_2") (pintype "power_in"))
    )
  )
)
